# TouScruino-v1.net
KiCad netlist of a schematic drawn in EAGLE
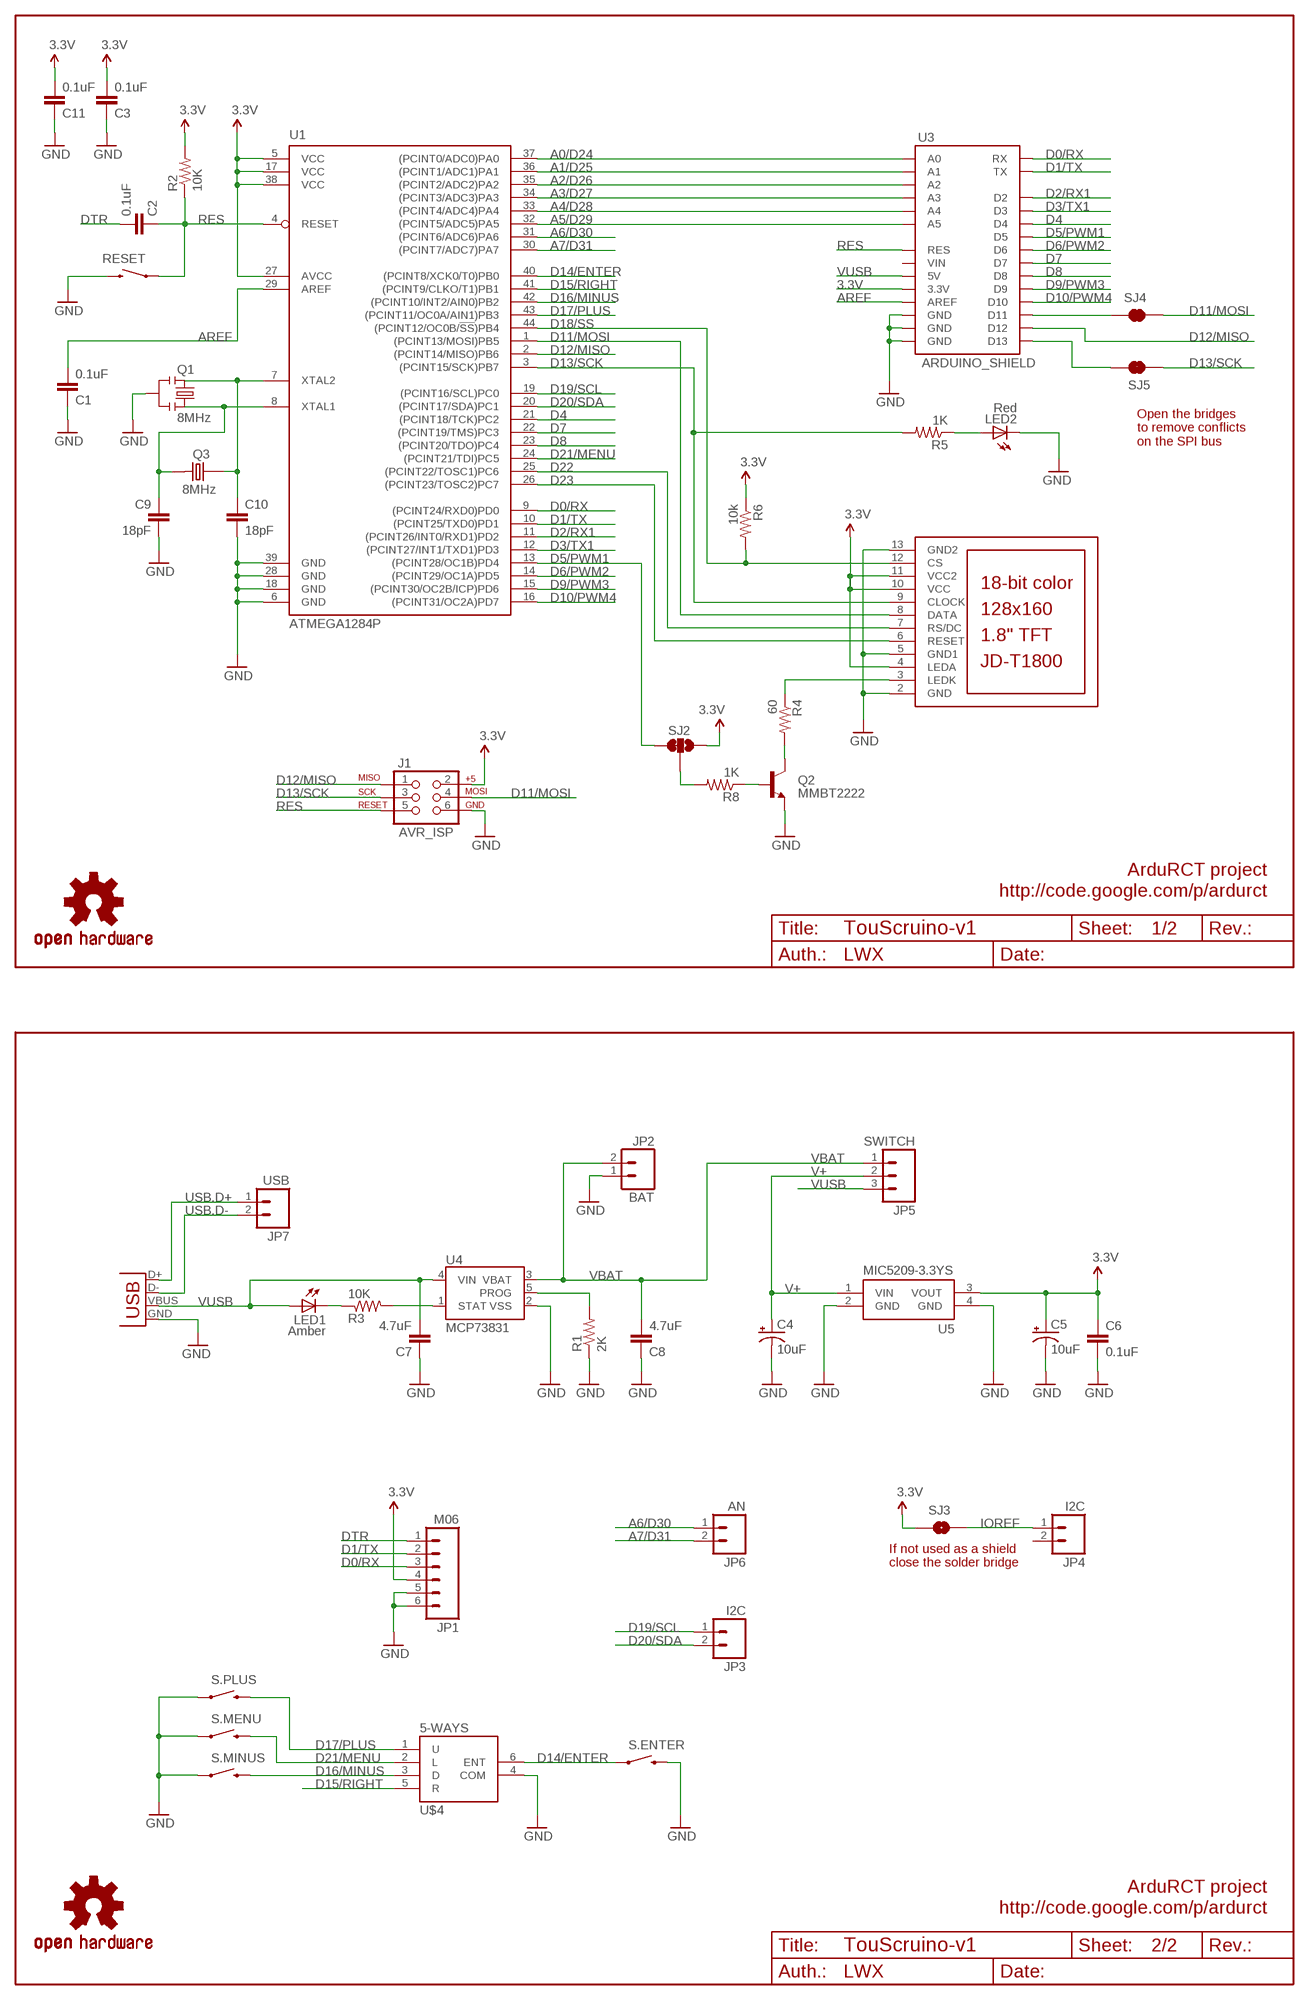
[diagram p0: schematic, sheet 1]

(export (version "E")
  (design (tool "Eeschema 10.0.6"))
  (components
    (comp (ref "C1")
      (value "0.1uF")
      (footprint "eagle-import:0805")
      (libsource (lib "eagle-import") (part "CAP0805"))
    )
    (comp (ref "C2")
      (value "0.1uF")
      (footprint "eagle-import:0805")
      (libsource (lib "eagle-import") (part "CAP0805"))
    )
    (comp (ref "C3")
      (value "0.1uF")
      (footprint "eagle-import:0805")
      (libsource (lib "eagle-import") (part "CAP0805"))
    )
    (comp (ref "C4")
      (value "10uF")
      (footprint "eagle-import:EIA3216")
      (libsource (lib "eagle-import") (part "CAP_POL1206"))
    )
    (comp (ref "C5")
      (value "10uF")
      (footprint "eagle-import:EIA3216")
      (libsource (lib "eagle-import") (part "CAP_POL1206"))
    )
    (comp (ref "C6")
      (value "0.1uF")
      (footprint "eagle-import:0805")
      (libsource (lib "eagle-import") (part "CAP0805"))
    )
    (comp (ref "C7")
      (value "4.7uF")
      (footprint "eagle-import:0805")
      (libsource (lib "eagle-import") (part "CAP0805"))
    )
    (comp (ref "C8")
      (value "4.7uF")
      (footprint "eagle-import:0805")
      (libsource (lib "eagle-import") (part "CAP0805"))
    )
    (comp (ref "C9")
      (value "18pF")
      (footprint "eagle-import:0603-CAP")
      (libsource (lib "eagle-import") (part "CAP0603-CAP"))
    )
    (comp (ref "C10")
      (value "18pF")
      (footprint "eagle-import:0603-CAP")
      (libsource (lib "eagle-import") (part "CAP0603-CAP"))
    )
    (comp (ref "C11")
      (value "0.1uF")
      (footprint "eagle-import:0805")
      (libsource (lib "eagle-import") (part "CAP0805"))
    )
    (comp (ref "J1")
      (value "AVR_ISP")
      (footprint "eagle-import:2X3")
      (libsource (lib "eagle-import") (part "AVR_SPI_PRG_6PTH"))
    )
    (comp (ref "JP1")
      (value "M06")
      (footprint "eagle-import:1X06")
      (libsource (lib "eagle-import") (part "M06"))
    )
    (comp (ref "JP2")
      (value "BAT")
      (footprint "eagle-import:JST-2-SMD")
      (libsource (lib "eagle-import") (part "M02-JST-2MM-SMT"))
    )
    (comp (ref "JP3")
      (value "I2C")
      (footprint "eagle-import:1X02")
      (libsource (lib "eagle-import") (part "M02"))
    )
    (comp (ref "JP4")
      (value "I2C")
      (footprint "eagle-import:1X02")
      (libsource (lib "eagle-import") (part "M02"))
    )
    (comp (ref "JP5")
      (value "SWITCH")
      (footprint "eagle-import:1X3_LONGPAD")
      (libsource (lib "eagle-import") (part "M03"))
    )
    (comp (ref "JP6")
      (value "AN")
      (footprint "eagle-import:1X02")
      (libsource (lib "eagle-import") (part "M02"))
    )
    (comp (ref "JP7")
      (value "USB")
      (footprint "eagle-import:1X02")
      (libsource (lib "eagle-import") (part "M02"))
    )
    (comp (ref "LCD1")
      (value "JD-T1800")
      (footprint "eagle-import:JD-T1800")
      (libsource (lib "eagle-import") (part "JD-T1800"))
    )
    (comp (ref "LED1")
      (value "Amber")
      (footprint "eagle-import:LED")
      (libsource (lib "eagle-import") (part "LED"))
    )
    (comp (ref "LED2")
      (value "Red")
      (footprint "eagle-import:LED-0805")
      (libsource (lib "eagle-import") (part "LED805"))
    )
    (comp (ref "Q1")
      (value "8MHz")
      (footprint "eagle-import:RESONATOR-SMD")
      (libsource (lib "eagle-import") (part "RESONATORSMD"))
    )
    (comp (ref "Q2")
      (value "MMBT2222")
      (footprint "eagle-import:SOT23-3")
      (libsource (lib "eagle-import") (part "TRANSISTOR_NPNSOT23-3"))
    )
    (comp (ref "Q3")
      (value "8MHz")
      (footprint "eagle-import:CRYSTAL_5X3.2")
      (libsource (lib "eagle-import") (part "CRYSTAL_5X3.2"))
    )
    (comp (ref "R1")
      (value "2K")
      (footprint "eagle-import:0805")
      (libsource (lib "eagle-import") (part "RESISTOR0805-RES"))
    )
    (comp (ref "R2")
      (value "10K")
      (footprint "eagle-import:0805")
      (libsource (lib "eagle-import") (part "RESISTOR0805-RES"))
    )
    (comp (ref "R3")
      (value "10K")
      (footprint "eagle-import:0805")
      (libsource (lib "eagle-import") (part "RESISTOR0805-RES"))
    )
    (comp (ref "R4")
      (value "60")
      (footprint "eagle-import:0805")
      (libsource (lib "eagle-import") (part "RESISTOR0805-RES"))
    )
    (comp (ref "R5")
      (value "1K")
      (footprint "eagle-import:0805")
      (libsource (lib "eagle-import") (part "RESISTOR0805-RES"))
    )
    (comp (ref "R6")
      (value "10k")
      (footprint "eagle-import:0805")
      (libsource (lib "eagle-import") (part "RESISTOR0805-RES"))
    )
    (comp (ref "R8")
      (value "1K")
      (footprint "eagle-import:0805")
      (libsource (lib "eagle-import") (part "RESISTOR0805-RES"))
    )
    (comp (ref "RESET")
      (value "SWITCH-MOMENTARY-2SMD")
      (footprint "eagle-import:TACTILE_SWITCH_SMD")
      (libsource (lib "eagle-import") (part "SWITCH-MOMENTARY-2SMD"))
    )
    (comp (ref "S.ENTER")
      (value "SWITCH_SMD")
      (footprint "eagle-import:TACTILE_SWITCH_SMD")
      (libsource (lib "eagle-import") (part "SWITCH_SMD"))
    )
    (comp (ref "S.MENU")
      (value "SWITCH_SMD")
      (footprint "eagle-import:TACTILE_SWITCH_SMD")
      (libsource (lib "eagle-import") (part "SWITCH_SMD"))
    )
    (comp (ref "S.MINUS")
      (value "SWITCH_SMD")
      (footprint "eagle-import:TACTILE_SWITCH_SMD")
      (libsource (lib "eagle-import") (part "SWITCH_SMD"))
    )
    (comp (ref "S.PLUS")
      (value "SWITCH_SMD")
      (footprint "eagle-import:TACTILE_SWITCH_SMD")
      (libsource (lib "eagle-import") (part "SWITCH_SMD"))
    )
    (comp (ref "SJ2")
      (value "SJ_2WAYS_1-2")
      (footprint "eagle-import:SJ_2WAYS_1-2_S")
      (libsource (lib "eagle-import") (part "SJ_2WAYS_1-2"))
    )
    (comp (ref "SJ3")
      (value "SOLDERJUMPERNO")
      (footprint "eagle-import:SJ_2S-NO")
      (libsource (lib "eagle-import") (part "SOLDERJUMPERNO"))
    )
    (comp (ref "SJ4")
      (value "SOLDERJUMPERTRACE")
      (footprint "eagle-import:SJ_2S-TRACE")
      (libsource (lib "eagle-import") (part "SOLDERJUMPERTRACE"))
    )
    (comp (ref "SJ5")
      (value "SOLDERJUMPERTRACE")
      (footprint "eagle-import:SJ_2S-TRACE")
      (libsource (lib "eagle-import") (part "SOLDERJUMPERTRACE"))
    )
    (comp (ref "U$3")
      (value "OSHW-LOGOM")
      (footprint "eagle-import:OSHW-LOGO-M")
      (libsource (lib "eagle-import") (part "OSHW-LOGOM"))
    )
    (comp (ref "U$4")
      (value "5-WAYS")
      (footprint "eagle-import:5-WAYS_ALPS")
      (libsource (lib "eagle-import") (part "5-WAYS"))
    )
    (comp (ref "U$5")
      (value "OSHW-LOGOM")
      (footprint "eagle-import:OSHW-LOGO-M")
      (libsource (lib "eagle-import") (part "OSHW-LOGOM"))
    )
    (comp (ref "U1")
      (value "ATMEGA1284P")
      (footprint "eagle-import:TQFP44")
      (libsource (lib "eagle-import") (part "ATMEGA324A"))
    )
    (comp (ref "U3")
      (value "ARDUINO_SHIELD")
      (footprint "eagle-import:ARDUINO_SHIELD")
      (libsource (lib "eagle-import") (part "ARDUINO_SHIELD"))
    )
    (comp (ref "U4")
      (value "MCP73831")
      (footprint "eagle-import:SOT23-5")
      (libsource (lib "eagle-import") (part "MCP73831"))
    )
    (comp (ref "U5")
      (value "MIC5209-3.3YS")
      (footprint "eagle-import:SOT223")
      (libsource (lib "eagle-import") (part "MIC5209"))
    )
    (comp (ref "X1")
      (value "USBSMD")
      (footprint "eagle-import:USB-MINIB")
      (libsource (lib "eagle-import") (part "USBSMD"))
    )
  )
  (nets
    (net (code "1") (name "/A0{slash}D24") (class "Default")
      (node (ref "U1") (pin "37") (pinfunction "(PCINT0/ADC0)PA0_37") (pintype "bidirectional"))
      (node (ref "U3") (pin "A0") (pinfunction "A0_A0") (pintype "bidirectional"))
    )
    (net (code "2") (name "/A1{slash}D25") (class "Default")
      (node (ref "U1") (pin "36") (pinfunction "(PCINT1/ADC1)PA1_36") (pintype "bidirectional"))
      (node (ref "U3") (pin "A1") (pinfunction "A1_A1") (pintype "bidirectional"))
    )
    (net (code "3") (name "/A2{slash}D26") (class "Default")
      (node (ref "U1") (pin "35") (pinfunction "(PCINT2/ADC2)PA2_35") (pintype "bidirectional"))
      (node (ref "U3") (pin "A2") (pinfunction "A2_A2") (pintype "bidirectional"))
    )
    (net (code "4") (name "/A3{slash}D27") (class "Default")
      (node (ref "U1") (pin "34") (pinfunction "(PCINT3/ADC3)PA3_34") (pintype "bidirectional"))
      (node (ref "U3") (pin "A3") (pinfunction "A3_A3") (pintype "bidirectional"))
    )
    (net (code "5") (name "/A4{slash}D28") (class "Default")
      (node (ref "U1") (pin "33") (pinfunction "(PCINT4/ADC4)PA4_33") (pintype "bidirectional"))
      (node (ref "U3") (pin "A4") (pinfunction "A4_A4") (pintype "bidirectional"))
    )
    (net (code "6") (name "/A5{slash}D29") (class "Default")
      (node (ref "U1") (pin "32") (pinfunction "(PCINT5/ADC5)PA5_32") (pintype "bidirectional"))
      (node (ref "U3") (pin "A5") (pinfunction "A5_A5") (pintype "bidirectional"))
    )
    (net (code "7") (name "/A6{slash}D30") (class "Default")
      (node (ref "JP6") (pin "1") (pinfunction "1_1") (pintype "passive"))
      (node (ref "U1") (pin "31") (pinfunction "(PCINT6/ADC6)PA6_31") (pintype "bidirectional"))
    )
    (net (code "8") (name "/A7{slash}D31") (class "Default")
      (node (ref "JP6") (pin "2") (pinfunction "2_2") (pintype "passive"))
      (node (ref "U1") (pin "30") (pinfunction "(PCINT7/ADC7)PA7_30") (pintype "bidirectional"))
    )
    (net (code "9") (name "/AREF") (class "Default")
      (node (ref "C1") (pin "2") (pinfunction "2_2") (pintype "passive"))
      (node (ref "U1") (pin "29") (pinfunction "AREF_29") (pintype "passive"))
      (node (ref "U3") (pin "AREF") (pinfunction "AREF_AREF") (pintype "bidirectional"))
    )
    (net (code "10") (name "/D0{slash}RX") (class "Default")
      (node (ref "JP1") (pin "3") (pinfunction "3_3") (pintype "passive"))
      (node (ref "U1") (pin "9") (pinfunction "(PCINT24/RXD0)PD0_9") (pintype "bidirectional"))
      (node (ref "U3") (pin "RX") (pinfunction "RX_RX") (pintype "bidirectional"))
    )
    (net (code "11") (name "/D1{slash}TX") (class "Default")
      (node (ref "JP1") (pin "2") (pinfunction "2_2") (pintype "passive"))
      (node (ref "U1") (pin "10") (pinfunction "(PCINT25/TXD0)PD1_10") (pintype "bidirectional"))
      (node (ref "U3") (pin "TX") (pinfunction "TX_TX") (pintype "bidirectional"))
    )
    (net (code "12") (name "/D2{slash}RX1") (class "Default")
      (node (ref "U1") (pin "11") (pinfunction "(PCINT26/INT0/RXD1)PD2_11") (pintype "bidirectional"))
      (node (ref "U3") (pin "D2") (pinfunction "D2_D2") (pintype "bidirectional"))
    )
    (net (code "13") (name "/D3{slash}TX1") (class "Default")
      (node (ref "U1") (pin "12") (pinfunction "(PCINT27/INT1/TXD1)PD3_12") (pintype "bidirectional"))
      (node (ref "U3") (pin "D3") (pinfunction "D3_D3") (pintype "bidirectional"))
    )
    (net (code "14") (name "/D4") (class "Default")
      (node (ref "U1") (pin "21") (pinfunction "(PCINT18/TCK)PC2_21") (pintype "output"))
      (node (ref "U3") (pin "D4") (pinfunction "D4_D4") (pintype "bidirectional"))
    )
    (net (code "15") (name "/D5{slash}PWM1") (class "Default")
      (node (ref "SJ2") (pin "1") (pinfunction "1_1") (pintype "passive"))
      (node (ref "U1") (pin "13") (pinfunction "(PCINT28/OC1B)PD4_13") (pintype "bidirectional"))
      (node (ref "U3") (pin "D5") (pinfunction "D5_D5") (pintype "bidirectional"))
    )
    (net (code "16") (name "/D6{slash}PWM2") (class "Default")
      (node (ref "U1") (pin "14") (pinfunction "(PCINT29/OC1A)PD5_14") (pintype "bidirectional"))
      (node (ref "U3") (pin "D6") (pinfunction "D6_D6") (pintype "bidirectional"))
    )
    (net (code "17") (name "/D7") (class "Default")
      (node (ref "U1") (pin "22") (pinfunction "(PCINT19/TMS)PC3_22") (pintype "output"))
      (node (ref "U3") (pin "D7") (pinfunction "D7_D7") (pintype "bidirectional"))
    )
    (net (code "18") (name "/D8") (class "Default")
      (node (ref "U1") (pin "23") (pinfunction "(PCINT20/TDO)PC4_23") (pintype "output"))
      (node (ref "U3") (pin "D8") (pinfunction "D8_D8") (pintype "bidirectional"))
    )
    (net (code "19") (name "/D9{slash}PWM3") (class "Default")
      (node (ref "U1") (pin "15") (pinfunction "(PCINT30/OC2B/ICP)PD6_15") (pintype "bidirectional"))
      (node (ref "U3") (pin "D9") (pinfunction "D9_D9") (pintype "bidirectional"))
    )
    (net (code "20") (name "/D10{slash}PWM4") (class "Default")
      (node (ref "U1") (pin "16") (pinfunction "(PCINT31/OC2A)PD7_16") (pintype "bidirectional"))
      (node (ref "U3") (pin "D10") (pinfunction "D10_D10") (pintype "bidirectional"))
    )
    (net (code "21") (name "/D11{slash}MOSI") (class "Default")
      (node (ref "J1") (pin "4") (pinfunction "4_4") (pintype "passive"))
      (node (ref "LCD1") (pin "8") (pinfunction "DATA_8") (pintype "bidirectional"))
      (node (ref "SJ4") (pin "2") (pinfunction "2_2") (pintype "passive"))
      (node (ref "U1") (pin "1") (pinfunction "(PCINT13/MOSI)PB5_1") (pintype "bidirectional"))
    )
    (net (code "22") (name "/D12{slash}MISO") (class "Default")
      (node (ref "J1") (pin "1") (pinfunction "1_1") (pintype "passive"))
      (node (ref "U1") (pin "2") (pinfunction "(PCINT14/MISO)PB6_2") (pintype "bidirectional"))
      (node (ref "U3") (pin "D12") (pinfunction "D12_D12") (pintype "bidirectional"))
    )
    (net (code "23") (name "/D13{slash}SCK") (class "Default")
      (node (ref "J1") (pin "3") (pinfunction "3_3") (pintype "passive"))
      (node (ref "LCD1") (pin "9") (pinfunction "CLOCK_9") (pintype "input"))
      (node (ref "R5") (pin "2") (pinfunction "2_2") (pintype "passive"))
      (node (ref "SJ5") (pin "1") (pinfunction "1_1") (pintype "passive"))
      (node (ref "U1") (pin "3") (pinfunction "(PCINT15/SCK)PB7_3") (pintype "bidirectional"))
    )
    (net (code "24") (name "/D14{slash}ENTER") (class "Default")
      (node (ref "S.ENTER") (pin "1") (pinfunction "1_1") (pintype "passive"))
      (node (ref "U$4") (pin "6") (pinfunction "ENT_6") (pintype "bidirectional"))
      (node (ref "U1") (pin "40") (pinfunction "(PCINT8/XCK0/T0)PB0_40") (pintype "bidirectional"))
    )
    (net (code "25") (name "/D15{slash}RIGHT") (class "Default")
      (node (ref "U$4") (pin "5") (pinfunction "R_5") (pintype "bidirectional"))
      (node (ref "U1") (pin "41") (pinfunction "(PCINT9/CLKO/T1)PB1_41") (pintype "bidirectional"))
    )
    (net (code "26") (name "/D16{slash}MINUS") (class "Default")
      (node (ref "S.MINUS") (pin "3") (pinfunction "2_3") (pintype "passive"))
      (node (ref "U$4") (pin "3") (pinfunction "D_3") (pintype "bidirectional"))
      (node (ref "U1") (pin "42") (pinfunction "(PCINT10/INT2/AIN0)PB2_42") (pintype "bidirectional"))
    )
    (net (code "27") (name "/D17{slash}PLUS") (class "Default")
      (node (ref "S.PLUS") (pin "3") (pinfunction "2_3") (pintype "passive"))
      (node (ref "U$4") (pin "1") (pinfunction "U_1") (pintype "bidirectional"))
      (node (ref "U1") (pin "43") (pinfunction "(PCINT11/OC0A/AIN1)PB3_43") (pintype "bidirectional"))
    )
    (net (code "28") (name "/D18{slash}SS") (class "Default")
      (node (ref "LCD1") (pin "12") (pinfunction "CS_12") (pintype "input"))
      (node (ref "R6") (pin "2") (pinfunction "2_2") (pintype "passive"))
      (node (ref "U1") (pin "44") (pinfunction "(PCINT12/OC0B/~{SS})PB4_44") (pintype "bidirectional"))
    )
    (net (code "29") (name "/D19{slash}SCL") (class "Default")
      (node (ref "JP3") (pin "1") (pinfunction "1_1") (pintype "passive"))
      (node (ref "U1") (pin "19") (pinfunction "(PCINT16/SCL)PC0_19") (pintype "output"))
    )
    (net (code "30") (name "/D20{slash}SDA") (class "Default")
      (node (ref "JP3") (pin "2") (pinfunction "2_2") (pintype "passive"))
      (node (ref "U1") (pin "20") (pinfunction "(PCINT17/SDA)PC1_20") (pintype "output"))
    )
    (net (code "31") (name "/D21{slash}MENU") (class "Default")
      (node (ref "S.MENU") (pin "3") (pinfunction "2_3") (pintype "passive"))
      (node (ref "U$4") (pin "2") (pinfunction "L_2") (pintype "bidirectional"))
      (node (ref "U1") (pin "24") (pinfunction "(PCINT21/TDI)PC5_24") (pintype "output"))
    )
    (net (code "32") (name "/D22") (class "Default")
      (node (ref "LCD1") (pin "7") (pinfunction "RS/DC_7") (pintype "input"))
      (node (ref "U1") (pin "25") (pinfunction "(PCINT22/TOSC1)PC6_25") (pintype "output"))
    )
    (net (code "33") (name "/D23") (class "Default")
      (node (ref "LCD1") (pin "6") (pinfunction "RESET_6") (pintype "input"))
      (node (ref "U1") (pin "26") (pinfunction "(PCINT23/TOSC2)PC7_26") (pintype "output"))
    )
    (net (code "34") (name "/DTR") (class "Default")
      (node (ref "C2") (pin "2") (pinfunction "2_2") (pintype "passive"))
      (node (ref "JP1") (pin "1") (pinfunction "1_1") (pintype "passive"))
    )
    (net (code "35") (name "/IOREF") (class "Default")
      (node (ref "JP4") (pin "1") (pinfunction "1_1") (pintype "passive"))
      (node (ref "SJ3") (pin "2") (pinfunction "2_2") (pintype "passive"))
    )
    (net (code "36") (name "/RES") (class "Default")
      (node (ref "C2") (pin "1") (pinfunction "1_1") (pintype "passive"))
      (node (ref "J1") (pin "5") (pinfunction "5_5") (pintype "passive"))
      (node (ref "R2") (pin "1") (pinfunction "1_1") (pintype "passive"))
      (node (ref "RESET") (pin "1") (pinfunction "1_1") (pintype "passive"))
      (node (ref "U1") (pin "4") (pinfunction "RESET_4") (pintype "input"))
      (node (ref "U3") (pin "RES") (pinfunction "RES_RES") (pintype "bidirectional"))
    )
    (net (code "37") (name "/USB.D+") (class "Default")
      (node (ref "JP7") (pin "1") (pinfunction "1_1") (pintype "passive"))
      (node (ref "X1") (pin "D+") (pinfunction "D+_D+") (pintype "bidirectional"))
    )
    (net (code "38") (name "/USB.D-") (class "Default")
      (node (ref "JP7") (pin "2") (pinfunction "2_2") (pintype "passive"))
      (node (ref "X1") (pin "D-") (pinfunction "D-_D-") (pintype "bidirectional"))
    )
    (net (code "39") (name "/V+") (class "Default")
      (node (ref "C4") (pin "A") (pinfunction "+_A") (pintype "passive"))
      (node (ref "JP5") (pin "2") (pinfunction "2_2") (pintype "passive"))
      (node (ref "U5") (pin "1") (pinfunction "VIN_1") (pintype "bidirectional"))
    )
    (net (code "40") (name "/VBAT") (class "Default")
      (node (ref "C8") (pin "2") (pinfunction "2_2") (pintype "passive"))
      (node (ref "JP2") (pin "2") (pinfunction "2_2") (pintype "passive"))
      (node (ref "JP5") (pin "1") (pinfunction "1_1") (pintype "passive"))
      (node (ref "U4") (pin "3") (pinfunction "VBAT_3") (pintype "power_in"))
    )
    (net (code "41") (name "/VUSB") (class "Default")
      (node (ref "C7") (pin "2") (pinfunction "2_2") (pintype "passive"))
      (node (ref "JP5") (pin "3") (pinfunction "3_3") (pintype "passive"))
      (node (ref "LED1") (pin "A1") (pinfunction "A_A1") (pintype "passive"))
      (node (ref "U3") (pin "5V") (pinfunction "5V_5V") (pintype "bidirectional"))
      (node (ref "U4") (pin "4") (pinfunction "VIN_4") (pintype "power_in"))
      (node (ref "X1") (pin "VBUS") (pinfunction "VBUS_VBUS") (pintype "bidirectional"))
    )
    (net (code "42") (name "3.3V") (class "Default")
      (node (ref "C11") (pin "2") (pinfunction "2_2") (pintype "passive"))
      (node (ref "C3") (pin "2") (pinfunction "2_2") (pintype "passive"))
      (node (ref "C5") (pin "A") (pinfunction "+_A") (pintype "passive"))
      (node (ref "C6") (pin "1") (pinfunction "1_1") (pintype "passive"))
      (node (ref "J1") (pin "2") (pinfunction "2_2") (pintype "passive"))
      (node (ref "JP1") (pin "4") (pinfunction "4_4") (pintype "passive"))
      (node (ref "LCD1") (pin "10") (pinfunction "VCC_10") (pintype "power_in"))
      (node (ref "LCD1") (pin "11") (pinfunction "VCC2_11") (pintype "power_in"))
      (node (ref "LCD1") (pin "4") (pinfunction "LEDA_4") (pintype "input"))
      (node (ref "R2") (pin "2") (pinfunction "2_2") (pintype "passive"))
      (node (ref "R6") (pin "1") (pinfunction "1_1") (pintype "passive"))
      (node (ref "SJ2") (pin "3") (pinfunction "3_3") (pintype "passive"))
      (node (ref "SJ3") (pin "1") (pinfunction "1_1") (pintype "passive"))
      (node (ref "U1") (pin "17") (pinfunction "VCC_17") (pintype "power_in"))
      (node (ref "U1") (pin "27") (pinfunction "AVCC_27") (pintype "power_in"))
      (node (ref "U1") (pin "38") (pinfunction "VCC_38") (pintype "power_in"))
      (node (ref "U1") (pin "5") (pinfunction "VCC_5") (pintype "power_in"))
      (node (ref "U3") (pin "3.3V") (pinfunction "3.3V_3.3V") (pintype "bidirectional"))
      (node (ref "U5") (pin "3") (pinfunction "VOUT_3") (pintype "bidirectional"))
    )
    (net (code "43") (name "GND") (class "Default")
      (node (ref "C1") (pin "1") (pinfunction "1_1") (pintype "passive"))
      (node (ref "C10") (pin "2") (pinfunction "2_2") (pintype "passive"))
      (node (ref "C11") (pin "1") (pinfunction "1_1") (pintype "passive"))
      (node (ref "C3") (pin "1") (pinfunction "1_1") (pintype "passive"))
      (node (ref "C4") (pin "C") (pinfunction "-_C") (pintype "passive"))
      (node (ref "C5") (pin "C") (pinfunction "-_C") (pintype "passive"))
      (node (ref "C6") (pin "2") (pinfunction "2_2") (pintype "passive"))
      (node (ref "C7") (pin "1") (pinfunction "1_1") (pintype "passive"))
      (node (ref "C8") (pin "1") (pinfunction "1_1") (pintype "passive"))
      (node (ref "C9") (pin "2") (pinfunction "2_2") (pintype "passive"))
      (node (ref "J1") (pin "6") (pinfunction "6_6") (pintype "passive"))
      (node (ref "JP1") (pin "5") (pinfunction "5_5") (pintype "passive"))
      (node (ref "JP1") (pin "6") (pinfunction "6_6") (pintype "passive"))
      (node (ref "JP2") (pin "1") (pinfunction "1_1") (pintype "passive"))
      (node (ref "LCD1") (pin "13") (pinfunction "GND2_13") (pintype "power_in"))
      (node (ref "LCD1") (pin "2") (pinfunction "GND_2") (pintype "power_in"))
      (node (ref "LCD1") (pin "5") (pinfunction "GND1_5") (pintype "power_in"))
      (node (ref "LED2") (pin "2") (pinfunction "C_2") (pintype "passive"))
      (node (ref "Q1") (pin "2") (pinfunction "2_2") (pintype "passive"))
      (node (ref "Q2") (pin "2") (pinfunction "E_2") (pintype "passive"))
      (node (ref "R1") (pin "1") (pinfunction "1_1") (pintype "passive"))
      (node (ref "RESET") (pin "3") (pinfunction "2_3") (pintype "passive"))
      (node (ref "S.ENTER") (pin "3") (pinfunction "2_3") (pintype "passive"))
      (node (ref "S.MENU") (pin "1") (pinfunction "1_1") (pintype "passive"))
      (node (ref "S.MINUS") (pin "1") (pinfunction "1_1") (pintype "passive"))
      (node (ref "S.PLUS") (pin "1") (pinfunction "1_1") (pintype "passive"))
      (node (ref "U$4") (pin "4") (pinfunction "COM_4") (pintype "bidirectional"))
      (node (ref "U1") (pin "18") (pinfunction "GND_18") (pintype "power_in"))
      (node (ref "U1") (pin "28") (pinfunction "GND_28") (pintype "power_in"))
      (node (ref "U1") (pin "39") (pinfunction "GND_39") (pintype "power_in"))
      (node (ref "U1") (pin "6") (pinfunction "GND_6") (pintype "power_in"))
      (node (ref "U3") (pin "GND@0") (pinfunction "GND_GND@0") (pintype "bidirectional"))
      (node (ref "U3") (pin "GND@1") (pinfunction "GND_GND@1") (pintype "bidirectional"))
      (node (ref "U3") (pin "GND@2") (pinfunction "GND_GND@2") (pintype "bidirectional"))
      (node (ref "U4") (pin "2") (pinfunction "VSS_2") (pintype "power_in"))
      (node (ref "U5") (pin "2") (pinfunction "GND_2") (pintype "bidirectional"))
      (node (ref "U5") (pin "4") (pinfunction "GND_4") (pintype "bidirectional"))
      (node (ref "X1") (pin "GND") (pinfunction "GND_GND") (pintype "bidirectional"))
    )
    (net (code "44") (name "Net-(LCD1-LEDK)") (class "Default")
      (node (ref "LCD1") (pin "3") (pinfunction "LEDK_3") (pintype "input"))
      (node (ref "R4") (pin "1") (pinfunction "1_1") (pintype "passive"))
    )
    (net (code "45") (name "Net-(LED1-C)") (class "Default")
      (node (ref "LED1") (pin "C1") (pinfunction "C_C1") (pintype "passive"))
      (node (ref "R3") (pin "1") (pinfunction "1_1") (pintype "passive"))
    )
    (net (code "46") (name "Net-(LED2-A)") (class "Default")
      (node (ref "LED2") (pin "1") (pinfunction "A_1") (pintype "passive"))
      (node (ref "R5") (pin "1") (pinfunction "1_1") (pintype "passive"))
    )
    (net (code "47") (name "Net-(Q2-B)") (class "Default")
      (node (ref "Q2") (pin "1") (pinfunction "B_1") (pintype "passive"))
      (node (ref "R8") (pin "1") (pinfunction "1_1") (pintype "passive"))
    )
    (net (code "48") (name "Net-(Q2-C)") (class "Default")
      (node (ref "Q2") (pin "3") (pinfunction "C_3") (pintype "passive"))
      (node (ref "R4") (pin "2") (pinfunction "2_2") (pintype "passive"))
    )
    (net (code "49") (name "Net-(R8-Pad2)") (class "Default")
      (node (ref "R8") (pin "2") (pinfunction "2_2") (pintype "passive"))
      (node (ref "SJ2") (pin "2") (pinfunction "2_2") (pintype "passive"))
    )
    (net (code "50") (name "Net-(SJ4-Pad1)") (class "Default")
      (node (ref "SJ4") (pin "1") (pinfunction "1_1") (pintype "passive"))
      (node (ref "U3") (pin "D11") (pinfunction "D11_D11") (pintype "bidirectional"))
    )
    (net (code "51") (name "Net-(SJ5-Pad2)") (class "Default")
      (node (ref "SJ5") (pin "2") (pinfunction "2_2") (pintype "passive"))
      (node (ref "U3") (pin "D13") (pinfunction "D13_D13") (pintype "bidirectional"))
    )
    (net (code "52") (name "Net-(U1-XTAL1)") (class "Default")
      (node (ref "C9") (pin "1") (pinfunction "1_1") (pintype "passive"))
      (node (ref "Q1") (pin "1") (pinfunction "1_1") (pintype "passive"))
      (node (ref "Q3") (pin "2") (pinfunction "2_2") (pintype "passive"))
      (node (ref "U1") (pin "8") (pinfunction "XTAL1_8") (pintype "bidirectional"))
    )
    (net (code "53") (name "Net-(U1-XTAL2)") (class "Default")
      (node (ref "C10") (pin "1") (pinfunction "1_1") (pintype "passive"))
      (node (ref "Q1") (pin "3") (pinfunction "3_3") (pintype "passive"))
      (node (ref "Q3") (pin "1") (pinfunction "1_1") (pintype "passive"))
      (node (ref "U1") (pin "7") (pinfunction "XTAL2_7") (pintype "bidirectional"))
    )
    (net (code "54") (name "Net-(U4-PROG)") (class "Default")
      (node (ref "R1") (pin "2") (pinfunction "2_2") (pintype "passive"))
      (node (ref "U4") (pin "5") (pinfunction "PROG_5") (pintype "input"))
    )
    (net (code "55") (name "Net-(U4-STAT)") (class "Default")
      (node (ref "R3") (pin "2") (pinfunction "2_2") (pintype "passive"))
      (node (ref "U4") (pin "1") (pinfunction "STAT_1") (pintype "output"))
    )
    (net (code "56") (name "unconnected-(JP4-Pad2)") (class "Default")
      (node (ref "JP4") (pin "2") (pinfunction "2_2") (pintype "passive"))
    )
    (net (code "57") (name "unconnected-(U3-PadVIN)") (class "Default")
      (node (ref "U3") (pin "VIN") (pinfunction "VIN_VIN") (pintype "bidirectional"))
    )
  )
)
